# GPS.net
KiCad netlist of a schematic drawn in Altium Designer
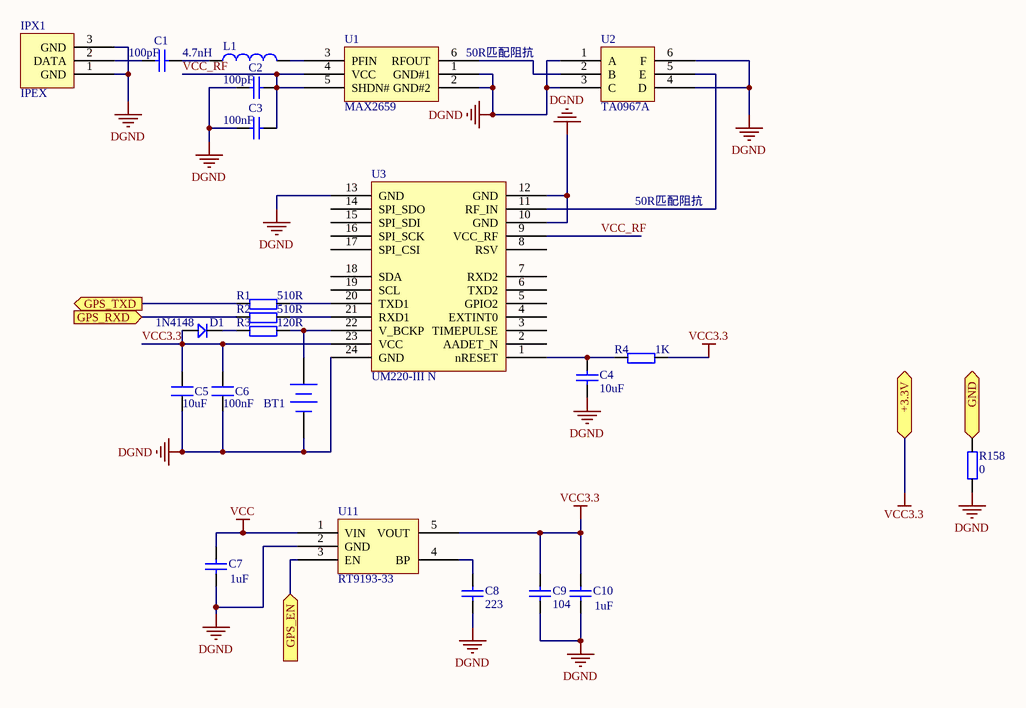
[diagram p0: GPS.SchDoc]

(export (version "E")
  (design (tool "Eeschema 10.0.6"))
  (components
    (comp (ref "BT1")
      (value "Battery")
      (footprint "BAT")
      (description "Multicell Battery")
      (fields (field (name "PUBLISHER") "Altium Limited"))
      (libsource (lib "Miscellaneous Devices") (part "Battery"))
    )
    (comp (ref "C1")
      (value "100pF")
      (footprint "0805")
      (description "Capacitor")
      (fields (field (name "Comment") "Cap") (field (name "PUBLISHER") "Altium Limited"))
      (libsource (lib "Miscellaneous Devices") (part "Cap"))
    )
    (comp (ref "C2")
      (value "100pF")
      (footprint "0805")
      (description "Capacitor")
      (fields (field (name "Comment") "Cap") (field (name "PUBLISHER") "Altium Limited"))
      (libsource (lib "Miscellaneous Devices") (part "Cap"))
    )
    (comp (ref "C3")
      (value "100nF")
      (footprint "0805")
      (description "Capacitor")
      (fields (field (name "Comment") "Cap") (field (name "PUBLISHER") "Altium Limited"))
      (libsource (lib "Miscellaneous Devices") (part "Cap"))
    )
    (comp (ref "C4")
      (value "10uF")
      (footprint "0805")
      (description "Capacitor")
      (fields (field (name "Comment") "Cap") (field (name "PUBLISHER") "Altium Limited"))
      (libsource (lib "Miscellaneous Devices") (part "Cap"))
    )
    (comp (ref "C5") (value "10uF") (footprint "0805") (libsource (lib "Explorer STM32F407封装库") (part "C")))
    (comp (ref "C6") (value "100nF") (footprint "0805") (libsource (lib "Explorer STM32F407封装库") (part "C")))
    (comp (ref "C7")
      (value "1uF")
      (footprint "0805")
      (description "Capacitor")
      (fields (field (name "Comment") "Cap") (field (name "PUBLISHER") "Altium Limited"))
      (libsource (lib "Miscellaneous Devices") (part "Cap"))
    )
    (comp (ref "C8")
      (value "223")
      (footprint "0805")
      (description "Capacitor")
      (fields (field (name "Comment") "Cap") (field (name "PUBLISHER") "Altium Limited"))
      (libsource (lib "Miscellaneous Devices") (part "Cap"))
    )
    (comp (ref "C9")
      (value "104")
      (footprint "0805")
      (description "Capacitor")
      (fields (field (name "Comment") "Cap") (field (name "PUBLISHER") "Altium Limited"))
      (libsource (lib "Miscellaneous Devices") (part "Cap"))
    )
    (comp (ref "C10")
      (value "1uF")
      (footprint "0805")
      (description "Capacitor")
      (fields (field (name "Comment") "Cap") (field (name "PUBLISHER") "Altium Limited"))
      (libsource (lib "Miscellaneous Devices") (part "Cap"))
    )
    (comp (ref "D1")
      (value "1N4148")
      (footprint "LC-SOD-323")
      (libsource (lib "ATK_S1216F8_BD_V1.1") (part "D"))
    )
    (comp (ref "IPX1") (value "IPEX") (footprint "IPEX") (libsource (lib "GPS") (part "IPX")))
    (comp (ref "L1")
      (value "4.7nH")
      (footprint "0805")
      (description "Inductor")
      (fields (field (name "PUBLISHER") "Altium Limited"))
      (libsource (lib "Miscellaneous Devices") (part "Inductor"))
    )
    (comp (ref "R1") (value "510R") (footprint "0805") (libsource (lib "Explorer STM32F407封装库") (part "R")))
    (comp (ref "R2") (value "510R") (footprint "0805") (libsource (lib "Explorer STM32F407封装库") (part "R")))
    (comp (ref "R3") (value "120R") (footprint "0805") (libsource (lib "ATK_S1216F8_BD_V1.1") (part "R")))
    (comp (ref "R4") (value "1K") (footprint "0805") (libsource (lib "Explorer STM32F407封装库") (part "R")))
    (comp (ref "R158") (value "0") (footprint "0805") (libsource (lib "Explorer STM32F407封装库") (part "R")))
    (comp (ref "U1") (value "MAX2659") (footprint "LC-uDFN-6") (libsource (lib "GPS") (part "MAX2659")))
    (comp (ref "U2") (value "TA0967A") (footprint "TA0967A") (libsource (lib "GPS") (part "TA0967A")))
    (comp (ref "U3")
      (value "UM220-III N")
      (footprint "UM220-III N")
      (libsource (lib "GPS") (part "Component_1"))
    )
    (comp (ref "U11") (value "RT9193-33") (footprint "RT9193-33") (libsource (lib "GPS") (part "RT9193-33")))
  )
  (nets
    (net (code "1") (name "/GND") (class "Default") (node (ref "R158") (pin "2") (pintype "passive")))
    (net (code "2") (name "/GPS_EN") (class "Default")
      (node (ref "U11") (pin "3") (pinfunction "EN_3") (pintype "passive"))
    )
    (net (code "3") (name "/GPS_RXD") (class "Default") (node (ref "R2") (pin "1") (pintype "passive")))
    (net (code "4") (name "/GPS_TXD") (class "Default") (node (ref "R1") (pin "1") (pintype "passive")))
    (net (code "5") (name "/VCC_RF") (class "Default")
      (node (ref "C2") (pin "2") (pinfunction "2_2") (pintype "passive"))
      (node (ref "C3") (pin "2") (pinfunction "2_2") (pintype "passive"))
      (node (ref "U1") (pin "4") (pinfunction "VCC_4") (pintype "passive"))
      (node (ref "U1") (pin "5") (pinfunction "SHDN#_5") (pintype "passive"))
      (node (ref "U3") (pin "9") (pinfunction "VCC_RF_9") (pintype "passive"))
    )
    (net (code "6") (name "DGND") (class "Default")
      (node (ref "BT1") (pin "2") (pinfunction "-_2") (pintype "passive"))
      (node (ref "C10") (pin "1") (pinfunction "1_1") (pintype "passive"))
      (node (ref "C2") (pin "1") (pinfunction "1_1") (pintype "passive"))
      (node (ref "C3") (pin "1") (pinfunction "1_1") (pintype "passive"))
      (node (ref "C4") (pin "1") (pinfunction "1_1") (pintype "passive"))
      (node (ref "C5") (pin "1") (pintype "passive"))
      (node (ref "C6") (pin "1") (pintype "passive"))
      (node (ref "C7") (pin "1") (pinfunction "1_1") (pintype "passive"))
      (node (ref "C8") (pin "1") (pinfunction "1_1") (pintype "passive"))
      (node (ref "C9") (pin "1") (pinfunction "1_1") (pintype "passive"))
      (node (ref "IPX1") (pin "1") (pinfunction "GND_1") (pintype "passive"))
      (node (ref "IPX1") (pin "3") (pinfunction "GND_3") (pintype "passive"))
      (node (ref "R158") (pin "1") (pintype "passive"))
      (node (ref "U1") (pin "1") (pinfunction "GND#1_1") (pintype "passive"))
      (node (ref "U1") (pin "2") (pinfunction "GND#2_2") (pintype "passive"))
      (node (ref "U11") (pin "2") (pinfunction "GND_2") (pintype "passive"))
      (node (ref "U2") (pin "1") (pinfunction "A_1") (pintype "passive"))
      (node (ref "U2") (pin "3") (pinfunction "C_3") (pintype "passive"))
      (node (ref "U2") (pin "4") (pinfunction "D_4") (pintype "passive"))
      (node (ref "U2") (pin "6") (pinfunction "F_6") (pintype "passive"))
      (node (ref "U3") (pin "10") (pinfunction "GND_10") (pintype "passive"))
      (node (ref "U3") (pin "12") (pinfunction "GND_12") (pintype "passive"))
      (node (ref "U3") (pin "13") (pinfunction "GND_13") (pintype "passive"))
      (node (ref "U3") (pin "24") (pinfunction "GND_24") (pintype "passive"))
    )
    (net (code "7") (name "Net-(BT1-+)") (class "Default")
      (node (ref "BT1") (pin "1") (pinfunction "+_1") (pintype "passive"))
      (node (ref "R3") (pin "2") (pintype "passive"))
      (node (ref "U3") (pin "22") (pinfunction "V_BCKP_22") (pintype "passive"))
    )
    (net (code "8") (name "Net-(C1-Pad2)") (class "Default")
      (node (ref "C1") (pin "2") (pinfunction "2_2") (pintype "passive"))
      (node (ref "L1") (pin "1") (pinfunction "1_1") (pintype "passive"))
    )
    (net (code "9") (name "Net-(D1-Pad2)") (class "Default")
      (node (ref "D1") (pin "2") (pintype "passive"))
      (node (ref "R3") (pin "1") (pintype "passive"))
    )
    (net (code "10") (name "Net-(IPX1-DATA)") (class "Default")
      (node (ref "C1") (pin "1") (pinfunction "1_1") (pintype "passive"))
      (node (ref "IPX1") (pin "2") (pinfunction "DATA_2") (pintype "passive"))
    )
    (net (code "11") (name "Net-(U1-PFIN)") (class "Default")
      (node (ref "L1") (pin "2") (pinfunction "2_2") (pintype "passive"))
      (node (ref "U1") (pin "3") (pinfunction "PFIN_3") (pintype "passive"))
    )
    (net (code "12") (name "Net-(U1-RFOUT)") (class "Default")
      (node (ref "U1") (pin "6") (pinfunction "RFOUT_6") (pintype "passive"))
      (node (ref "U2") (pin "2") (pinfunction "B_2") (pintype "passive"))
    )
    (net (code "13") (name "Net-(U2-E)") (class "Default")
      (node (ref "U2") (pin "5") (pinfunction "E_5") (pintype "passive"))
      (node (ref "U3") (pin "11") (pinfunction "RF_IN_11") (pintype "passive"))
    )
    (net (code "14") (name "Net-(U3-RXD1)") (class "Default")
      (node (ref "R2") (pin "2") (pintype "passive"))
      (node (ref "U3") (pin "21") (pinfunction "RXD1_21") (pintype "passive"))
    )
    (net (code "15") (name "Net-(U3-TXD1)") (class "Default")
      (node (ref "R1") (pin "2") (pintype "passive"))
      (node (ref "U3") (pin "20") (pinfunction "TXD1_20") (pintype "passive"))
    )
    (net (code "16") (name "Net-(U3-nRESET)") (class "Default")
      (node (ref "C4") (pin "2") (pinfunction "2_2") (pintype "passive"))
      (node (ref "R4") (pin "1") (pintype "passive"))
      (node (ref "U3") (pin "1") (pinfunction "nRESET_1") (pintype "passive"))
    )
    (net (code "17") (name "Net-(U11-BP)") (class "Default")
      (node (ref "C8") (pin "2") (pinfunction "2_2") (pintype "passive"))
      (node (ref "U11") (pin "4") (pinfunction "BP_4") (pintype "passive"))
    )
    (net (code "18") (name "VCC") (class "Default")
      (node (ref "C7") (pin "2") (pinfunction "2_2") (pintype "passive"))
      (node (ref "U11") (pin "1") (pinfunction "VIN_1") (pintype "passive"))
    )
    (net (code "19") (name "VCC3.3") (class "Default")
      (node (ref "C10") (pin "2") (pinfunction "2_2") (pintype "passive"))
      (node (ref "C5") (pin "2") (pintype "passive"))
      (node (ref "C6") (pin "2") (pintype "passive"))
      (node (ref "C9") (pin "2") (pinfunction "2_2") (pintype "passive"))
      (node (ref "D1") (pin "1") (pintype "passive"))
      (node (ref "R4") (pin "2") (pintype "passive"))
      (node (ref "U11") (pin "5") (pinfunction "VOUT_5") (pintype "passive"))
      (node (ref "U3") (pin "23") (pinfunction "VCC_23") (pintype "passive"))
    )
    (net (code "20") (name "unconnected-(U3-AADET_N-Pad2)") (class "Default")
      (node (ref "U3") (pin "2") (pinfunction "AADET_N_2") (pintype "passive"))
    )
    (net (code "21") (name "unconnected-(U3-EXTINT0-Pad4)") (class "Default")
      (node (ref "U3") (pin "4") (pinfunction "EXTINT0_4") (pintype "passive"))
    )
    (net (code "22") (name "unconnected-(U3-GPIO2-Pad5)") (class "Default")
      (node (ref "U3") (pin "5") (pinfunction "GPIO2_5") (pintype "passive"))
    )
    (net (code "23") (name "unconnected-(U3-RSV-Pad8)") (class "Default")
      (node (ref "U3") (pin "8") (pinfunction "RSV_8") (pintype "passive"))
    )
    (net (code "24") (name "unconnected-(U3-RXD2-Pad7)") (class "Default")
      (node (ref "U3") (pin "7") (pinfunction "RXD2_7") (pintype "passive"))
    )
    (net (code "25") (name "unconnected-(U3-SCL-Pad19)") (class "Default")
      (node (ref "U3") (pin "19") (pinfunction "SCL_19") (pintype "passive"))
    )
    (net (code "26") (name "unconnected-(U3-SDA-Pad18)") (class "Default")
      (node (ref "U3") (pin "18") (pinfunction "SDA_18") (pintype "passive"))
    )
    (net (code "27") (name "unconnected-(U3-SPI_CSI-Pad17)") (class "Default")
      (node (ref "U3") (pin "17") (pinfunction "SPI_CSI_17") (pintype "passive"))
    )
    (net (code "28") (name "unconnected-(U3-SPI_SCK-Pad16)") (class "Default")
      (node (ref "U3") (pin "16") (pinfunction "SPI_SCK_16") (pintype "passive"))
    )
    (net (code "29") (name "unconnected-(U3-SPI_SDI-Pad15)") (class "Default")
      (node (ref "U3") (pin "15") (pinfunction "SPI_SDI_15") (pintype "passive"))
    )
    (net (code "30") (name "unconnected-(U3-SPI_SDO-Pad14)") (class "Default")
      (node (ref "U3") (pin "14") (pinfunction "SPI_SDO_14") (pintype "passive"))
    )
    (net (code "31") (name "unconnected-(U3-TIMEPULSE-Pad3)") (class "Default")
      (node (ref "U3") (pin "3") (pinfunction "TIMEPULSE_3") (pintype "passive"))
    )
    (net (code "32") (name "unconnected-(U3-TXD2-Pad6)") (class "Default")
      (node (ref "U3") (pin "6") (pinfunction "TXD2_6") (pintype "passive"))
    )
  )
)
